# NodeIO.net
KiCad netlist of a schematic drawn in Altium Designer
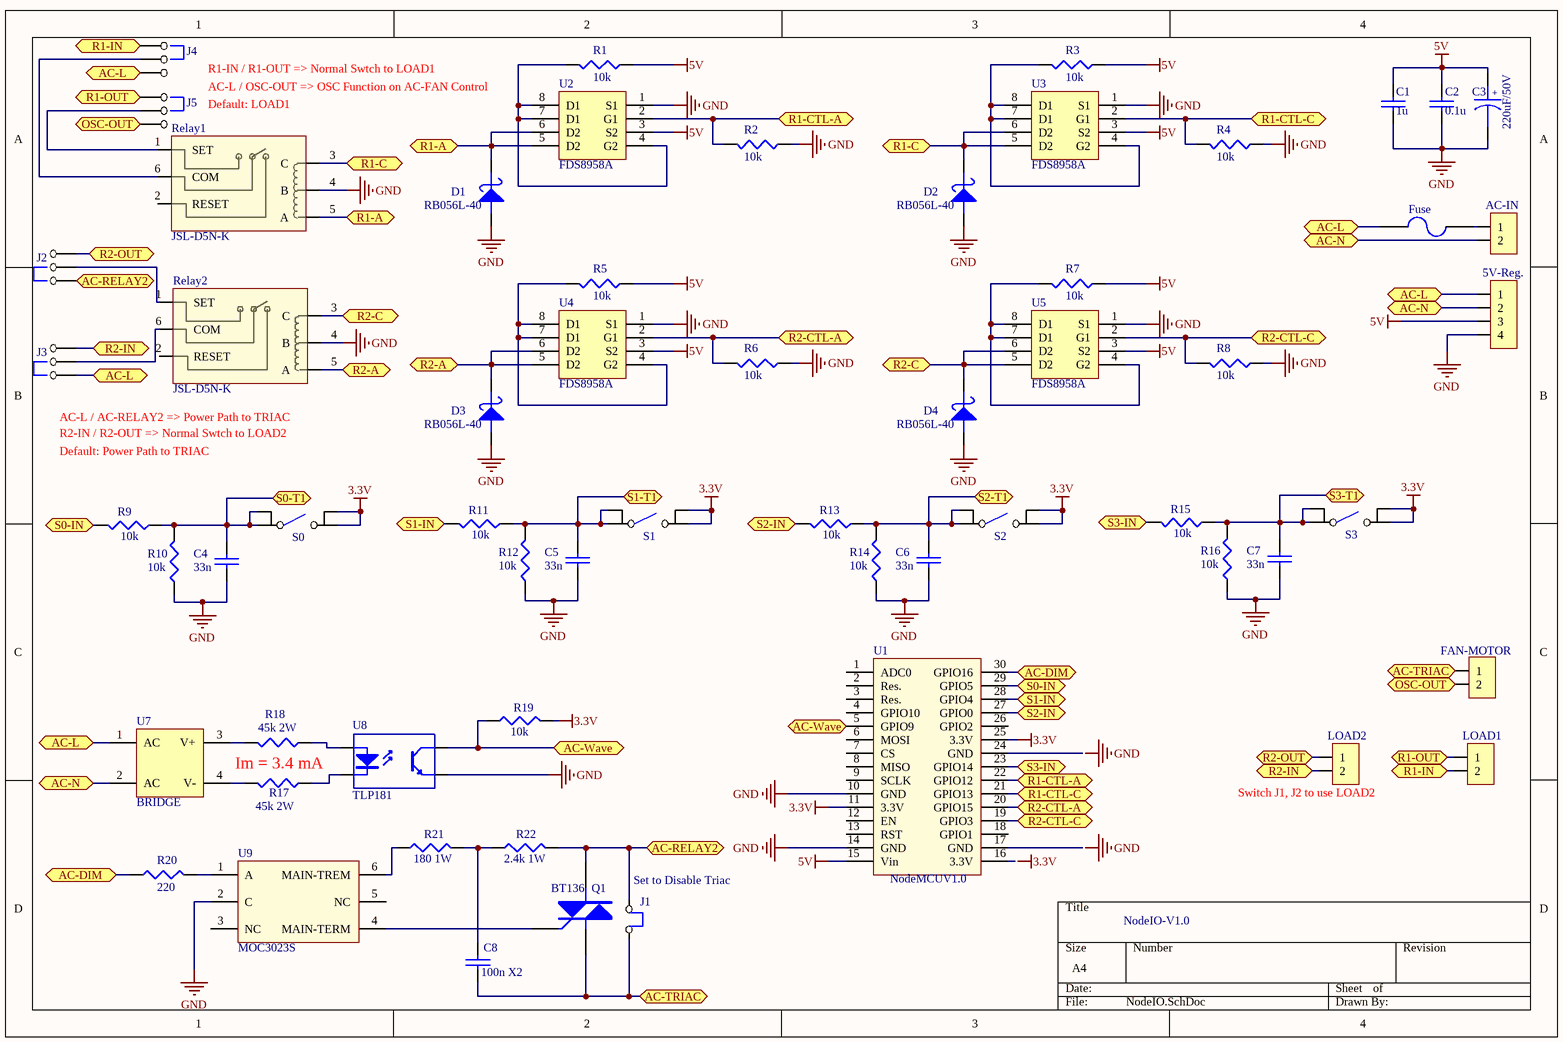
[diagram p0: NodeIO.SchDoc]

(export (version "E")
  (design (tool "Eeschema 10.0.6"))
  (components
    (comp (ref "5V-Reg.") (value "~") (libsource (lib "Mind-Innovation") (part "CON4")))
    (comp (ref "AC-IN") (value "~") (libsource (lib "Mind-Innovation") (part "CON2")))
    (comp (ref "C1")
      (value "1u")
      (footprint "C_SMD_2012-0805")
      (libsource (lib "Mind-Innovation") (part "CAP"))
    )
    (comp (ref "C2")
      (value "0.1u")
      (footprint "C_SMD_2012-0805")
      (libsource (lib "Mind-Innovation") (part "CAP"))
    )
    (comp (ref "C3")
      (value "220uF/50V")
      (footprint "C_ECEL_G")
      (description "UWT1C221MCL1GS")
      (libsource (lib "Mind-Innovation") (part "C_Eletro"))
    )
    (comp (ref "C4")
      (value "33n")
      (footprint "C_SMD_2012-0805")
      (libsource (lib "Mind-Innovation") (part "CAP"))
    )
    (comp (ref "C5")
      (value "33n")
      (footprint "C_SMD_2012-0805")
      (libsource (lib "Mind-Innovation") (part "CAP"))
    )
    (comp (ref "C6")
      (value "33n")
      (footprint "C_SMD_2012-0805")
      (libsource (lib "Mind-Innovation") (part "CAP"))
    )
    (comp (ref "C7")
      (value "33n")
      (footprint "C_SMD_2012-0805")
      (libsource (lib "Mind-Innovation") (part "CAP"))
    )
    (comp (ref "C8")
      (value "100n X2")
      (footprint "Cap-B32933-EPCOS")
      (libsource (lib "Mind-Innovation") (part "CAP"))
    )
    (comp (ref "D1")
      (value "RB056L-40")
      (footprint "DIODE_RB056L-40TE25")
      (description "Diode_Schottky")
      (fields (field (name "MANUFACTURER") "ROHM Semiconductor"))
      (libsource (lib "Mind-Innovation") (part "Diode_Schottky"))
    )
    (comp (ref "D2")
      (value "RB056L-40")
      (footprint "DIODE_RB056L-40TE25")
      (description "Diode_Schottky")
      (fields (field (name "MANUFACTURER") "ROHM Semiconductor"))
      (libsource (lib "Mind-Innovation") (part "Diode_Schottky"))
    )
    (comp (ref "D3")
      (value "RB056L-40")
      (footprint "DIODE_RB056L-40TE25")
      (description "Diode_Schottky")
      (fields (field (name "MANUFACTURER") "ROHM Semiconductor"))
      (libsource (lib "Mind-Innovation") (part "Diode_Schottky"))
    )
    (comp (ref "D4")
      (value "RB056L-40")
      (footprint "DIODE_RB056L-40TE25")
      (description "Diode_Schottky")
      (fields (field (name "MANUFACTURER") "ROHM Semiconductor"))
      (libsource (lib "Mind-Innovation") (part "Diode_Schottky"))
    )
    (comp (ref "FAN-MOTOR") (value "~") (libsource (lib "Mind-Innovation") (part "CON2")))
    (comp (ref "Fuse")
      (value "~")
      (fields (field (name "MANUFACTURER") "TELE LONG") (field (name "RELATE_PART") "0054-0030-0"))
      (libsource (lib "Mind-Innovation") (part "Fuse"))
    )
    (comp (ref "J1")
      (value "~")
      (footprint "JUMP 7.5A")
      (description "Jumper2")
      (libsource (lib "Mind-Innovation") (part "Jumper2"))
    )
    (comp (ref "J2")
      (value "~")
      (footprint "JP_3S_2.0mm")
      (description "Jumper3")
      (libsource (lib "Mind-Innovation") (part "Jumper3"))
    )
    (comp (ref "J3")
      (value "~")
      (footprint "JP_3S_2.0mm")
      (description "Jumper3")
      (libsource (lib "Mind-Innovation") (part "Jumper3"))
    )
    (comp (ref "J4")
      (value "~")
      (footprint "JP_3S_2.0mm")
      (description "Jumper3")
      (libsource (lib "Mind-Innovation") (part "Jumper3"))
    )
    (comp (ref "J5")
      (value "~")
      (footprint "JP_3S_2.0mm")
      (description "Jumper3")
      (libsource (lib "Mind-Innovation") (part "Jumper3"))
    )
    (comp (ref "LOAD1") (value "~") (libsource (lib "Mind-Innovation") (part "CON2")))
    (comp (ref "LOAD2") (value "~") (libsource (lib "Mind-Innovation") (part "CON2")))
    (comp (ref "Q1")
      (value "BT136")
      (footprint "TO220V")
      (fields (field (name "MANUFACTURER") "PHILIPS/NXP"))
      (libsource (lib "Mind-Innovation") (part "TRIAC"))
    )
    (comp (ref "R1")
      (value "10k")
      (footprint "R_2012-0805")
      (libsource (lib "Mind-Innovation") (part "Resistor"))
    )
    (comp (ref "R2")
      (value "10k")
      (footprint "R_2012-0805")
      (libsource (lib "Mind-Innovation") (part "Resistor"))
    )
    (comp (ref "R3")
      (value "10k")
      (footprint "R_2012-0805")
      (libsource (lib "Mind-Innovation") (part "Resistor"))
    )
    (comp (ref "R4")
      (value "10k")
      (footprint "R_2012-0805")
      (libsource (lib "Mind-Innovation") (part "Resistor"))
    )
    (comp (ref "R5")
      (value "10k")
      (footprint "R_2012-0805")
      (libsource (lib "Mind-Innovation") (part "Resistor"))
    )
    (comp (ref "R6")
      (value "10k")
      (footprint "R_2012-0805")
      (libsource (lib "Mind-Innovation") (part "Resistor"))
    )
    (comp (ref "R7")
      (value "10k")
      (footprint "R_2012-0805")
      (libsource (lib "Mind-Innovation") (part "Resistor"))
    )
    (comp (ref "R8")
      (value "10k")
      (footprint "R_2012-0805")
      (libsource (lib "Mind-Innovation") (part "Resistor"))
    )
    (comp (ref "R9")
      (value "10k")
      (footprint "R_2012-0805")
      (libsource (lib "Mind-Innovation") (part "Resistor"))
    )
    (comp (ref "R10")
      (value "10k")
      (footprint "R_2012-0805")
      (libsource (lib "Mind-Innovation") (part "Resistor"))
    )
    (comp (ref "R11")
      (value "10k")
      (footprint "R_2012-0805")
      (libsource (lib "Mind-Innovation") (part "Resistor"))
    )
    (comp (ref "R12")
      (value "10k")
      (footprint "R_2012-0805")
      (libsource (lib "Mind-Innovation") (part "Resistor"))
    )
    (comp (ref "R13")
      (value "10k")
      (footprint "R_2012-0805")
      (libsource (lib "Mind-Innovation") (part "Resistor"))
    )
    (comp (ref "R14")
      (value "10k")
      (footprint "R_2012-0805")
      (libsource (lib "Mind-Innovation") (part "Resistor"))
    )
    (comp (ref "R15")
      (value "10k")
      (footprint "R_2012-0805")
      (libsource (lib "Mind-Innovation") (part "Resistor"))
    )
    (comp (ref "R16")
      (value "10k")
      (footprint "R_2012-0805")
      (libsource (lib "Mind-Innovation") (part "Resistor"))
    )
    (comp (ref "R17")
      (value "45k 2W")
      (footprint "R_2W_TH")
      (libsource (lib "Mind-Innovation") (part "Resistor"))
    )
    (comp (ref "R18")
      (value "45k 2W")
      (footprint "R_2W_TH")
      (libsource (lib "Mind-Innovation") (part "Resistor"))
    )
    (comp (ref "R19")
      (value "10k")
      (footprint "R_2012-0805")
      (libsource (lib "Mind-Innovation") (part "Resistor"))
    )
    (comp (ref "R20")
      (value "220")
      (footprint "R_2012-0805")
      (libsource (lib "Mind-Innovation") (part "Resistor"))
    )
    (comp (ref "R21")
      (value "180 1W")
      (footprint "R_2W_TH")
      (libsource (lib "Mind-Innovation") (part "Resistor"))
    )
    (comp (ref "R22")
      (value "2.4k 1W")
      (footprint "R_2W_TH")
      (libsource (lib "Mind-Innovation") (part "Resistor"))
    )
    (comp (ref "Relay1")
      (value "JSL-D5N-K")
      (footprint "RELAY-JSL-DxxN-K")
      (fields (field (name "MANUFACTURER") "FUJITSU COMPONENTS"))
      (libsource (lib "Mind-Innovation") (part "Latching-Relay-2Coils"))
    )
    (comp (ref "Relay2")
      (value "JSL-D5N-K")
      (footprint "RELAY-JSL-DxxN-K")
      (fields (field (name "MANUFACTURER") "FUJITSU COMPONENTS"))
      (libsource (lib "Mind-Innovation") (part "Latching-Relay-2Coils"))
    )
    (comp (ref "S0")
      (value "SW-SPST_4_PIN")
      (footprint "SW-TD-06XB-Z")
      (fields (field (name "MANUFACTURER") "WEALTH METAL"))
      (libsource (lib "Mind-Innovation") (part "SW-SPST_4_PIN"))
    )
    (comp (ref "S1")
      (value "SW-SPST_4_PIN")
      (footprint "SW-TD-06XB-Z")
      (fields (field (name "MANUFACTURER") "WEALTH METAL"))
      (libsource (lib "Mind-Innovation") (part "SW-SPST_4_PIN"))
    )
    (comp (ref "S2")
      (value "SW-SPST_4_PIN")
      (footprint "SW-TD-06XB-Z")
      (fields (field (name "MANUFACTURER") "WEALTH METAL"))
      (libsource (lib "Mind-Innovation") (part "SW-SPST_4_PIN"))
    )
    (comp (ref "S3")
      (value "SW-SPST_4_PIN")
      (footprint "SW-TD-06XB-Z")
      (fields (field (name "MANUFACTURER") "WEALTH METAL"))
      (libsource (lib "Mind-Innovation") (part "SW-SPST_4_PIN"))
    )
    (comp (ref "U1")
      (value "NodeMCUV1.0")
      (footprint "NodeMCUV1.0")
      (libsource (lib "Mind-Innovation") (part "NodeMCUV1.0"))
    )
    (comp (ref "U2")
      (value "FDS8958A")
      (footprint "SO-8")
      (fields (field (name "MANUFACTURER") "FAIRCHILD"))
      (libsource (lib "Mind-Innovation") (part "FDS8958A"))
    )
    (comp (ref "U3")
      (value "FDS8958A")
      (footprint "SO-8")
      (fields (field (name "MANUFACTURER") "FAIRCHILD"))
      (libsource (lib "Mind-Innovation") (part "FDS8958A"))
    )
    (comp (ref "U4")
      (value "FDS8958A")
      (footprint "SO-8")
      (fields (field (name "MANUFACTURER") "FAIRCHILD"))
      (libsource (lib "Mind-Innovation") (part "FDS8958A"))
    )
    (comp (ref "U5")
      (value "FDS8958A")
      (footprint "SO-8")
      (fields (field (name "MANUFACTURER") "FAIRCHILD"))
      (libsource (lib "Mind-Innovation") (part "FDS8958A"))
    )
    (comp (ref "U7")
      (value "BRIDGE")
      (footprint "Bridge-MB8S")
      (description "Diode Bridge")
      (libsource (lib "Mind-Innovation") (part "BRIDGE_2"))
    )
    (comp (ref "U8")
      (value "TLP181")
      (footprint "TLP181")
      (fields (field (name "MANUFACTURER") "TOSHIBA"))
      (libsource (lib "Krit_library") (part "TLP181"))
    )
    (comp (ref "U9")
      (value "MOC3023S")
      (footprint "SOIC6")
      (fields (field (name "MANUFACTURER") "LITE-ON"))
      (libsource (lib "Mind-Innovation") (part "MOC30xx"))
    )
  )
  (nets
    (net (code "1") (name "/AC-DIM") (class "Default")
      (node (ref "R20") (pin "1") (pinfunction "1_1") (pintype "passive"))
      (node (ref "U1") (pin "30") (pinfunction "GPIO16_30") (pintype "passive"))
    )
    (net (code "2") (name "/AC-L") (class "Default")
      (node (ref "5V-Reg.") (pin "1") (pinfunction "1_1") (pintype "passive"))
      (node (ref "Fuse") (pin "1") (pinfunction "1_1") (pintype "passive"))
      (node (ref "J3") (pin "1") (pinfunction "1_1") (pintype "passive"))
      (node (ref "J4") (pin "3") (pinfunction "3_3") (pintype "passive"))
      (node (ref "U7") (pin "1") (pinfunction "AC_1") (pintype "passive"))
    )
    (net (code "3") (name "/AC-N") (class "Default")
      (node (ref "5V-Reg.") (pin "2") (pinfunction "2_2") (pintype "passive"))
      (node (ref "AC-IN") (pin "2") (pinfunction "2_2") (pintype "passive"))
      (node (ref "U7") (pin "2") (pinfunction "AC_2") (pintype "passive"))
    )
    (net (code "4") (name "/AC-RELAY2") (class "Default")
      (node (ref "J1") (pin "1") (pinfunction "1_1") (pintype "passive"))
      (node (ref "J2") (pin "1") (pinfunction "1_1") (pintype "passive"))
      (node (ref "Q1") (pin "2") (pinfunction "A2_2") (pintype "passive"))
      (node (ref "R22") (pin "2") (pinfunction "2_2") (pintype "passive"))
    )
    (net (code "5") (name "/AC-TRIAC") (class "Default")
      (node (ref "C8") (pin "1") (pinfunction "1_1") (pintype "passive"))
      (node (ref "FAN-MOTOR") (pin "1") (pinfunction "1_1") (pintype "passive"))
      (node (ref "J1") (pin "2") (pinfunction "2_2") (pintype "passive"))
      (node (ref "Q1") (pin "1") (pinfunction "A1_1") (pintype "passive"))
    )
    (net (code "6") (name "/AC-Wave") (class "Default")
      (node (ref "R19") (pin "1") (pinfunction "1_1") (pintype "passive"))
      (node (ref "U1") (pin "5") (pinfunction "GPIO9_5") (pintype "passive"))
      (node (ref "U8") (pin "4") (pinfunction "C_4") (pintype "passive"))
    )
    (net (code "7") (name "/OSC-OUT") (class "Default")
      (node (ref "FAN-MOTOR") (pin "2") (pinfunction "2_2") (pintype "passive"))
      (node (ref "J5") (pin "3") (pinfunction "3_3") (pintype "passive"))
    )
    (net (code "8") (name "/R1-A") (class "Default")
      (node (ref "D1") (pin "2") (pinfunction "K_2") (pintype "passive"))
      (node (ref "Relay1") (pin "5") (pinfunction "A_5") (pintype "passive"))
      (node (ref "U2") (pin "5") (pinfunction "D2_5") (pintype "passive"))
      (node (ref "U2") (pin "6") (pinfunction "D2_6") (pintype "passive"))
    )
    (net (code "9") (name "/R1-C") (class "Default")
      (node (ref "D2") (pin "2") (pinfunction "K_2") (pintype "passive"))
      (node (ref "Relay1") (pin "3") (pinfunction "C_3") (pintype "passive"))
      (node (ref "U3") (pin "5") (pinfunction "D2_5") (pintype "passive"))
      (node (ref "U3") (pin "6") (pinfunction "D2_6") (pintype "passive"))
    )
    (net (code "10") (name "/R1-CTL-A") (class "Default")
      (node (ref "R2") (pin "2") (pinfunction "2_2") (pintype "passive"))
      (node (ref "U1") (pin "22") (pinfunction "GPIO12_22") (pintype "passive"))
      (node (ref "U2") (pin "2") (pinfunction "G1_2") (pintype "passive"))
    )
    (net (code "11") (name "/R1-CTL-C") (class "Default")
      (node (ref "R4") (pin "2") (pinfunction "2_2") (pintype "passive"))
      (node (ref "U1") (pin "21") (pinfunction "GPIO13_21") (pintype "passive"))
      (node (ref "U3") (pin "2") (pinfunction "G1_2") (pintype "passive"))
    )
    (net (code "12") (name "/R1-IN") (class "Default")
      (node (ref "J4") (pin "1") (pinfunction "1_1") (pintype "passive"))
      (node (ref "LOAD1") (pin "2") (pinfunction "2_2") (pintype "passive"))
    )
    (net (code "13") (name "/R1-OUT") (class "Default")
      (node (ref "J5") (pin "1") (pinfunction "1_1") (pintype "passive"))
      (node (ref "LOAD1") (pin "1") (pinfunction "1_1") (pintype "passive"))
    )
    (net (code "14") (name "/R2-A") (class "Default")
      (node (ref "D3") (pin "2") (pinfunction "K_2") (pintype "passive"))
      (node (ref "Relay2") (pin "5") (pinfunction "A_5") (pintype "passive"))
      (node (ref "U4") (pin "5") (pinfunction "D2_5") (pintype "passive"))
      (node (ref "U4") (pin "6") (pinfunction "D2_6") (pintype "passive"))
    )
    (net (code "15") (name "/R2-C") (class "Default")
      (node (ref "D4") (pin "2") (pinfunction "K_2") (pintype "passive"))
      (node (ref "Relay2") (pin "3") (pinfunction "C_3") (pintype "passive"))
      (node (ref "U5") (pin "5") (pinfunction "D2_5") (pintype "passive"))
      (node (ref "U5") (pin "6") (pinfunction "D2_6") (pintype "passive"))
    )
    (net (code "16") (name "/R2-CTL-A") (class "Default")
      (node (ref "R6") (pin "2") (pinfunction "2_2") (pintype "passive"))
      (node (ref "U1") (pin "20") (pinfunction "GPIO15_20") (pintype "passive"))
      (node (ref "U4") (pin "2") (pinfunction "G1_2") (pintype "passive"))
    )
    (net (code "17") (name "/R2-CTL-C") (class "Default")
      (node (ref "R8") (pin "2") (pinfunction "2_2") (pintype "passive"))
      (node (ref "U1") (pin "19") (pinfunction "GPIO3_19") (pintype "passive"))
      (node (ref "U5") (pin "2") (pinfunction "G1_2") (pintype "passive"))
    )
    (net (code "18") (name "/R2-IN") (class "Default")
      (node (ref "J3") (pin "3") (pinfunction "3_3") (pintype "passive"))
      (node (ref "LOAD2") (pin "2") (pinfunction "2_2") (pintype "passive"))
    )
    (net (code "19") (name "/R2-OUT") (class "Default")
      (node (ref "J2") (pin "3") (pinfunction "3_3") (pintype "passive"))
      (node (ref "LOAD2") (pin "1") (pinfunction "1_1") (pintype "passive"))
    )
    (net (code "20") (name "/S0-IN") (class "Default")
      (node (ref "R9") (pin "2") (pinfunction "2_2") (pintype "passive"))
      (node (ref "U1") (pin "29") (pinfunction "GPIO5_29") (pintype "passive"))
    )
    (net (code "21") (name "/S0-T1") (class "Default")
      (node (ref "C4") (pin "1") (pinfunction "1_1") (pintype "passive"))
      (node (ref "R10") (pin "2") (pinfunction "2_2") (pintype "passive"))
      (node (ref "R9") (pin "1") (pinfunction "1_1") (pintype "passive"))
      (node (ref "S0") (pin "1") (pinfunction "1_1") (pintype "passive"))
      (node (ref "S0") (pin "2") (pinfunction "2_2") (pintype "passive"))
    )
    (net (code "22") (name "/S1-IN") (class "Default")
      (node (ref "R11") (pin "2") (pinfunction "2_2") (pintype "passive"))
      (node (ref "U1") (pin "28") (pinfunction "GPIO4_28") (pintype "passive"))
    )
    (net (code "23") (name "/S1-T1") (class "Default")
      (node (ref "C5") (pin "1") (pinfunction "1_1") (pintype "passive"))
      (node (ref "R11") (pin "1") (pinfunction "1_1") (pintype "passive"))
      (node (ref "R12") (pin "2") (pinfunction "2_2") (pintype "passive"))
      (node (ref "S1") (pin "1") (pinfunction "1_1") (pintype "passive"))
      (node (ref "S1") (pin "2") (pinfunction "2_2") (pintype "passive"))
    )
    (net (code "24") (name "/S2-IN") (class "Default")
      (node (ref "R13") (pin "2") (pinfunction "2_2") (pintype "passive"))
      (node (ref "U1") (pin "27") (pinfunction "GPIO0_27") (pintype "passive"))
    )
    (net (code "25") (name "/S2-T1") (class "Default")
      (node (ref "C6") (pin "1") (pinfunction "1_1") (pintype "passive"))
      (node (ref "R13") (pin "1") (pinfunction "1_1") (pintype "passive"))
      (node (ref "R14") (pin "2") (pinfunction "2_2") (pintype "passive"))
      (node (ref "S2") (pin "1") (pinfunction "1_1") (pintype "passive"))
      (node (ref "S2") (pin "2") (pinfunction "2_2") (pintype "passive"))
    )
    (net (code "26") (name "/S3-IN") (class "Default")
      (node (ref "R15") (pin "2") (pinfunction "2_2") (pintype "passive"))
      (node (ref "U1") (pin "23") (pinfunction "GPIO14_23") (pintype "passive"))
    )
    (net (code "27") (name "/S3-T1") (class "Default")
      (node (ref "C7") (pin "1") (pinfunction "1_1") (pintype "passive"))
      (node (ref "R15") (pin "1") (pinfunction "1_1") (pintype "passive"))
      (node (ref "R16") (pin "2") (pinfunction "2_2") (pintype "passive"))
      (node (ref "S3") (pin "1") (pinfunction "1_1") (pintype "passive"))
      (node (ref "S3") (pin "2") (pinfunction "2_2") (pintype "passive"))
    )
    (net (code "28") (name "3.3V") (class "Default")
      (node (ref "R19") (pin "2") (pinfunction "2_2") (pintype "passive"))
      (node (ref "S0") (pin "3") (pinfunction "3_3") (pintype "passive"))
      (node (ref "S0") (pin "4") (pinfunction "4_4") (pintype "passive"))
      (node (ref "S1") (pin "3") (pinfunction "3_3") (pintype "passive"))
      (node (ref "S1") (pin "4") (pinfunction "4_4") (pintype "passive"))
      (node (ref "S2") (pin "3") (pinfunction "3_3") (pintype "passive"))
      (node (ref "S2") (pin "4") (pinfunction "4_4") (pintype "passive"))
      (node (ref "S3") (pin "3") (pinfunction "3_3") (pintype "passive"))
      (node (ref "S3") (pin "4") (pinfunction "4_4") (pintype "passive"))
      (node (ref "U1") (pin "11") (pinfunction "3.3V_11") (pintype "passive"))
      (node (ref "U1") (pin "25") (pinfunction "3.3V_25") (pintype "passive"))
    )
    (net (code "29") (name "5V") (class "Default")
      (node (ref "5V-Reg.") (pin "3") (pinfunction "3_3") (pintype "passive"))
      (node (ref "C1") (pin "1") (pinfunction "1_1") (pintype "passive"))
      (node (ref "C2") (pin "1") (pinfunction "1_1") (pintype "passive"))
      (node (ref "C3") (pin "1") (pinfunction "1_1") (pintype "passive"))
      (node (ref "R1") (pin "1") (pinfunction "1_1") (pintype "passive"))
      (node (ref "R3") (pin "1") (pinfunction "1_1") (pintype "passive"))
      (node (ref "R5") (pin "1") (pinfunction "1_1") (pintype "passive"))
      (node (ref "R7") (pin "1") (pinfunction "1_1") (pintype "passive"))
      (node (ref "U1") (pin "15") (pinfunction "Vin_15") (pintype "passive"))
      (node (ref "U2") (pin "3") (pinfunction "S2_3") (pintype "passive"))
      (node (ref "U3") (pin "3") (pinfunction "S2_3") (pintype "passive"))
      (node (ref "U4") (pin "3") (pinfunction "S2_3") (pintype "passive"))
      (node (ref "U5") (pin "3") (pinfunction "S2_3") (pintype "passive"))
    )
    (net (code "30") (name "GND") (class "Default")
      (node (ref "5V-Reg.") (pin "4") (pinfunction "4_4") (pintype "passive"))
      (node (ref "C1") (pin "2") (pinfunction "2_2") (pintype "passive"))
      (node (ref "C2") (pin "2") (pinfunction "2_2") (pintype "passive"))
      (node (ref "C3") (pin "2") (pinfunction "2_2") (pintype "passive"))
      (node (ref "C4") (pin "2") (pinfunction "2_2") (pintype "passive"))
      (node (ref "C5") (pin "2") (pinfunction "2_2") (pintype "passive"))
      (node (ref "C6") (pin "2") (pinfunction "2_2") (pintype "passive"))
      (node (ref "C7") (pin "2") (pinfunction "2_2") (pintype "passive"))
      (node (ref "D1") (pin "1") (pinfunction "A_1") (pintype "passive"))
      (node (ref "D2") (pin "1") (pinfunction "A_1") (pintype "passive"))
      (node (ref "D3") (pin "1") (pinfunction "A_1") (pintype "passive"))
      (node (ref "D4") (pin "1") (pinfunction "A_1") (pintype "passive"))
      (node (ref "R10") (pin "1") (pinfunction "1_1") (pintype "passive"))
      (node (ref "R12") (pin "1") (pinfunction "1_1") (pintype "passive"))
      (node (ref "R14") (pin "1") (pinfunction "1_1") (pintype "passive"))
      (node (ref "R16") (pin "1") (pinfunction "1_1") (pintype "passive"))
      (node (ref "R2") (pin "1") (pinfunction "1_1") (pintype "passive"))
      (node (ref "R4") (pin "1") (pinfunction "1_1") (pintype "passive"))
      (node (ref "R6") (pin "1") (pinfunction "1_1") (pintype "passive"))
      (node (ref "R8") (pin "1") (pinfunction "1_1") (pintype "passive"))
      (node (ref "Relay1") (pin "4") (pinfunction "B_4") (pintype "passive"))
      (node (ref "Relay2") (pin "4") (pinfunction "B_4") (pintype "passive"))
      (node (ref "U1") (pin "10") (pinfunction "GND_10") (pintype "passive"))
      (node (ref "U1") (pin "14") (pinfunction "GND_14") (pintype "passive"))
      (node (ref "U2") (pin "1") (pinfunction "S1_1") (pintype "passive"))
      (node (ref "U3") (pin "1") (pinfunction "S1_1") (pintype "passive"))
      (node (ref "U4") (pin "1") (pinfunction "S1_1") (pintype "passive"))
      (node (ref "U5") (pin "1") (pinfunction "S1_1") (pintype "passive"))
      (node (ref "U8") (pin "3") (pinfunction "E_3") (pintype "passive"))
      (node (ref "U9") (pin "2") (pinfunction "C_2") (pintype "passive"))
    )
    (net (code "31") (name "Net-(AC-IN-Pad1)") (class "Default")
      (node (ref "AC-IN") (pin "1") (pinfunction "1_1") (pintype "passive"))
      (node (ref "Fuse") (pin "2") (pinfunction "2_2") (pintype "passive"))
    )
    (net (code "32") (name "Net-(C8-Pad2)") (class "Default")
      (node (ref "C8") (pin "2") (pinfunction "2_2") (pintype "passive"))
      (node (ref "R21") (pin "2") (pinfunction "2_2") (pintype "passive"))
      (node (ref "R22") (pin "1") (pinfunction "1_1") (pintype "passive"))
    )
    (net (code "33") (name "Net-(Q1-G)") (class "Default")
      (node (ref "Q1") (pin "3") (pinfunction "G_3") (pintype "passive"))
      (node (ref "U9") (pin "4") (pinfunction "MAIN-TERM_4") (pintype "passive"))
    )
    (net (code "34") (name "Net-(Relay1-COM)") (class "Default")
      (node (ref "J4") (pin "2") (pinfunction "2_2") (pintype "passive"))
      (node (ref "Relay1") (pin "6") (pinfunction "COM_6") (pintype "passive"))
    )
    (net (code "35") (name "Net-(Relay1-SET)") (class "Default")
      (node (ref "J5") (pin "2") (pinfunction "2_2") (pintype "passive"))
      (node (ref "Relay1") (pin "1") (pinfunction "SET_1") (pintype "passive"))
    )
    (net (code "36") (name "Net-(Relay2-COM)") (class "Default")
      (node (ref "J3") (pin "2") (pinfunction "2_2") (pintype "passive"))
      (node (ref "Relay2") (pin "6") (pinfunction "COM_6") (pintype "passive"))
    )
    (net (code "37") (name "Net-(Relay2-SET)") (class "Default")
      (node (ref "J2") (pin "2") (pinfunction "2_2") (pintype "passive"))
      (node (ref "Relay2") (pin "1") (pinfunction "SET_1") (pintype "passive"))
    )
    (net (code "38") (name "Net-(U2-G2)") (class "Default")
      (node (ref "R1") (pin "2") (pinfunction "2_2") (pintype "passive"))
      (node (ref "U2") (pin "4") (pinfunction "G2_4") (pintype "passive"))
      (node (ref "U2") (pin "7") (pinfunction "D1_7") (pintype "passive"))
      (node (ref "U2") (pin "8") (pinfunction "D1_8") (pintype "passive"))
    )
    (net (code "39") (name "Net-(U3-G2)") (class "Default")
      (node (ref "R3") (pin "2") (pinfunction "2_2") (pintype "passive"))
      (node (ref "U3") (pin "4") (pinfunction "G2_4") (pintype "passive"))
      (node (ref "U3") (pin "7") (pinfunction "D1_7") (pintype "passive"))
      (node (ref "U3") (pin "8") (pinfunction "D1_8") (pintype "passive"))
    )
    (net (code "40") (name "Net-(U4-G2)") (class "Default")
      (node (ref "R5") (pin "2") (pinfunction "2_2") (pintype "passive"))
      (node (ref "U4") (pin "4") (pinfunction "G2_4") (pintype "passive"))
      (node (ref "U4") (pin "7") (pinfunction "D1_7") (pintype "passive"))
      (node (ref "U4") (pin "8") (pinfunction "D1_8") (pintype "passive"))
    )
    (net (code "41") (name "Net-(U5-G2)") (class "Default")
      (node (ref "R7") (pin "2") (pinfunction "2_2") (pintype "passive"))
      (node (ref "U5") (pin "4") (pinfunction "G2_4") (pintype "passive"))
      (node (ref "U5") (pin "7") (pinfunction "D1_7") (pintype "passive"))
      (node (ref "U5") (pin "8") (pinfunction "D1_8") (pintype "passive"))
    )
    (net (code "42") (name "Net-(U7-V+)") (class "Default")
      (node (ref "R18") (pin "2") (pinfunction "2_2") (pintype "passive"))
      (node (ref "U7") (pin "3") (pinfunction "V+_3") (pintype "passive"))
    )
    (net (code "43") (name "Net-(U7-V-)") (class "Default")
      (node (ref "R17") (pin "2") (pinfunction "2_2") (pintype "passive"))
      (node (ref "U7") (pin "4") (pinfunction "V-_4") (pintype "passive"))
    )
    (net (code "44") (name "Net-(U8-A)") (class "Default")
      (node (ref "R18") (pin "1") (pinfunction "1_1") (pintype "passive"))
      (node (ref "U8") (pin "1") (pinfunction "A_1") (pintype "passive"))
    )
    (net (code "45") (name "Net-(U8-K)") (class "Default")
      (node (ref "R17") (pin "1") (pinfunction "1_1") (pintype "passive"))
      (node (ref "U8") (pin "2") (pinfunction "K_2") (pintype "passive"))
    )
    (net (code "46") (name "Net-(U9-A)") (class "Default")
      (node (ref "R20") (pin "2") (pinfunction "2_2") (pintype "passive"))
      (node (ref "U9") (pin "1") (pinfunction "A_1") (pintype "passive"))
    )
    (net (code "47") (name "Net-(U9-MAIN-TREM)") (class "Default")
      (node (ref "R21") (pin "1") (pinfunction "1_1") (pintype "passive"))
      (node (ref "U9") (pin "6") (pinfunction "MAIN-TREM_6") (pintype "passive"))
    )
    (net (code "48") (name "unconnected-(Relay1-RESET-Pad2)") (class "Default")
      (node (ref "Relay1") (pin "2") (pinfunction "RESET_2") (pintype "passive"))
    )
    (net (code "49") (name "unconnected-(Relay2-RESET-Pad2)") (class "Default")
      (node (ref "Relay2") (pin "2") (pinfunction "RESET_2") (pintype "passive"))
    )
    (net (code "50") (name "unconnected-(U1-3.3V-Pad16)") (class "Default")
      (node (ref "U1") (pin "16") (pinfunction "3.3V_16") (pintype "passive"))
    )
    (net (code "51") (name "unconnected-(U1-ADC0-Pad1)") (class "Default")
      (node (ref "U1") (pin "1") (pinfunction "ADC0_1") (pintype "passive"))
    )
    (net (code "52") (name "unconnected-(U1-CS-Pad7)") (class "Default")
      (node (ref "U1") (pin "7") (pinfunction "CS_7") (pintype "passive"))
    )
    (net (code "53") (name "unconnected-(U1-EN-Pad12)") (class "Default")
      (node (ref "U1") (pin "12") (pinfunction "EN_12") (pintype "passive"))
    )
    (net (code "54") (name "unconnected-(U1-GND-Pad17)") (class "Default")
      (node (ref "U1") (pin "17") (pinfunction "GND_17") (pintype "passive"))
    )
    (net (code "55") (name "unconnected-(U1-GND-Pad24)") (class "Default")
      (node (ref "U1") (pin "24") (pinfunction "GND_24") (pintype "passive"))
    )
    (net (code "56") (name "unconnected-(U1-GPIO1-Pad18)") (class "Default")
      (node (ref "U1") (pin "18") (pinfunction "GPIO1_18") (pintype "passive"))
    )
    (net (code "57") (name "unconnected-(U1-GPIO2-Pad26)") (class "Default")
      (node (ref "U1") (pin "26") (pinfunction "GPIO2_26") (pintype "passive"))
    )
    (net (code "58") (name "unconnected-(U1-GPIO10-Pad4)") (class "Default")
      (node (ref "U1") (pin "4") (pinfunction "GPIO10_4") (pintype "passive"))
    )
    (net (code "59") (name "unconnected-(U1-MISO-Pad8)") (class "Default")
      (node (ref "U1") (pin "8") (pinfunction "MISO_8") (pintype "passive"))
    )
    (net (code "60") (name "unconnected-(U1-MOSI-Pad6)") (class "Default")
      (node (ref "U1") (pin "6") (pinfunction "MOSI_6") (pintype "passive"))
    )
    (net (code "61") (name "unconnected-(U1-RST-Pad13)") (class "Default")
      (node (ref "U1") (pin "13") (pinfunction "RST_13") (pintype "passive"))
    )
    (net (code "62") (name "unconnected-(U1-Res.-Pad2)") (class "Default")
      (node (ref "U1") (pin "2") (pinfunction "Res._2") (pintype "passive"))
    )
    (net (code "63") (name "unconnected-(U1-Res.-Pad3)") (class "Default")
      (node (ref "U1") (pin "3") (pinfunction "Res._3") (pintype "passive"))
    )
    (net (code "64") (name "unconnected-(U1-SCLK-Pad9)") (class "Default")
      (node (ref "U1") (pin "9") (pinfunction "SCLK_9") (pintype "passive"))
    )
    (net (code "65") (name "unconnected-(U9-NC-Pad3)") (class "Default")
      (node (ref "U9") (pin "3") (pinfunction "NC_3") (pintype "passive"))
    )
    (net (code "66") (name "unconnected-(U9-NC-Pad5)") (class "Default")
      (node (ref "U9") (pin "5") (pinfunction "NC_5") (pintype "passive"))
    )
  )
)
